# Adafruit_PowerBoost_1000C_Rev_B.net
KiCad netlist of a schematic drawn in EAGLE
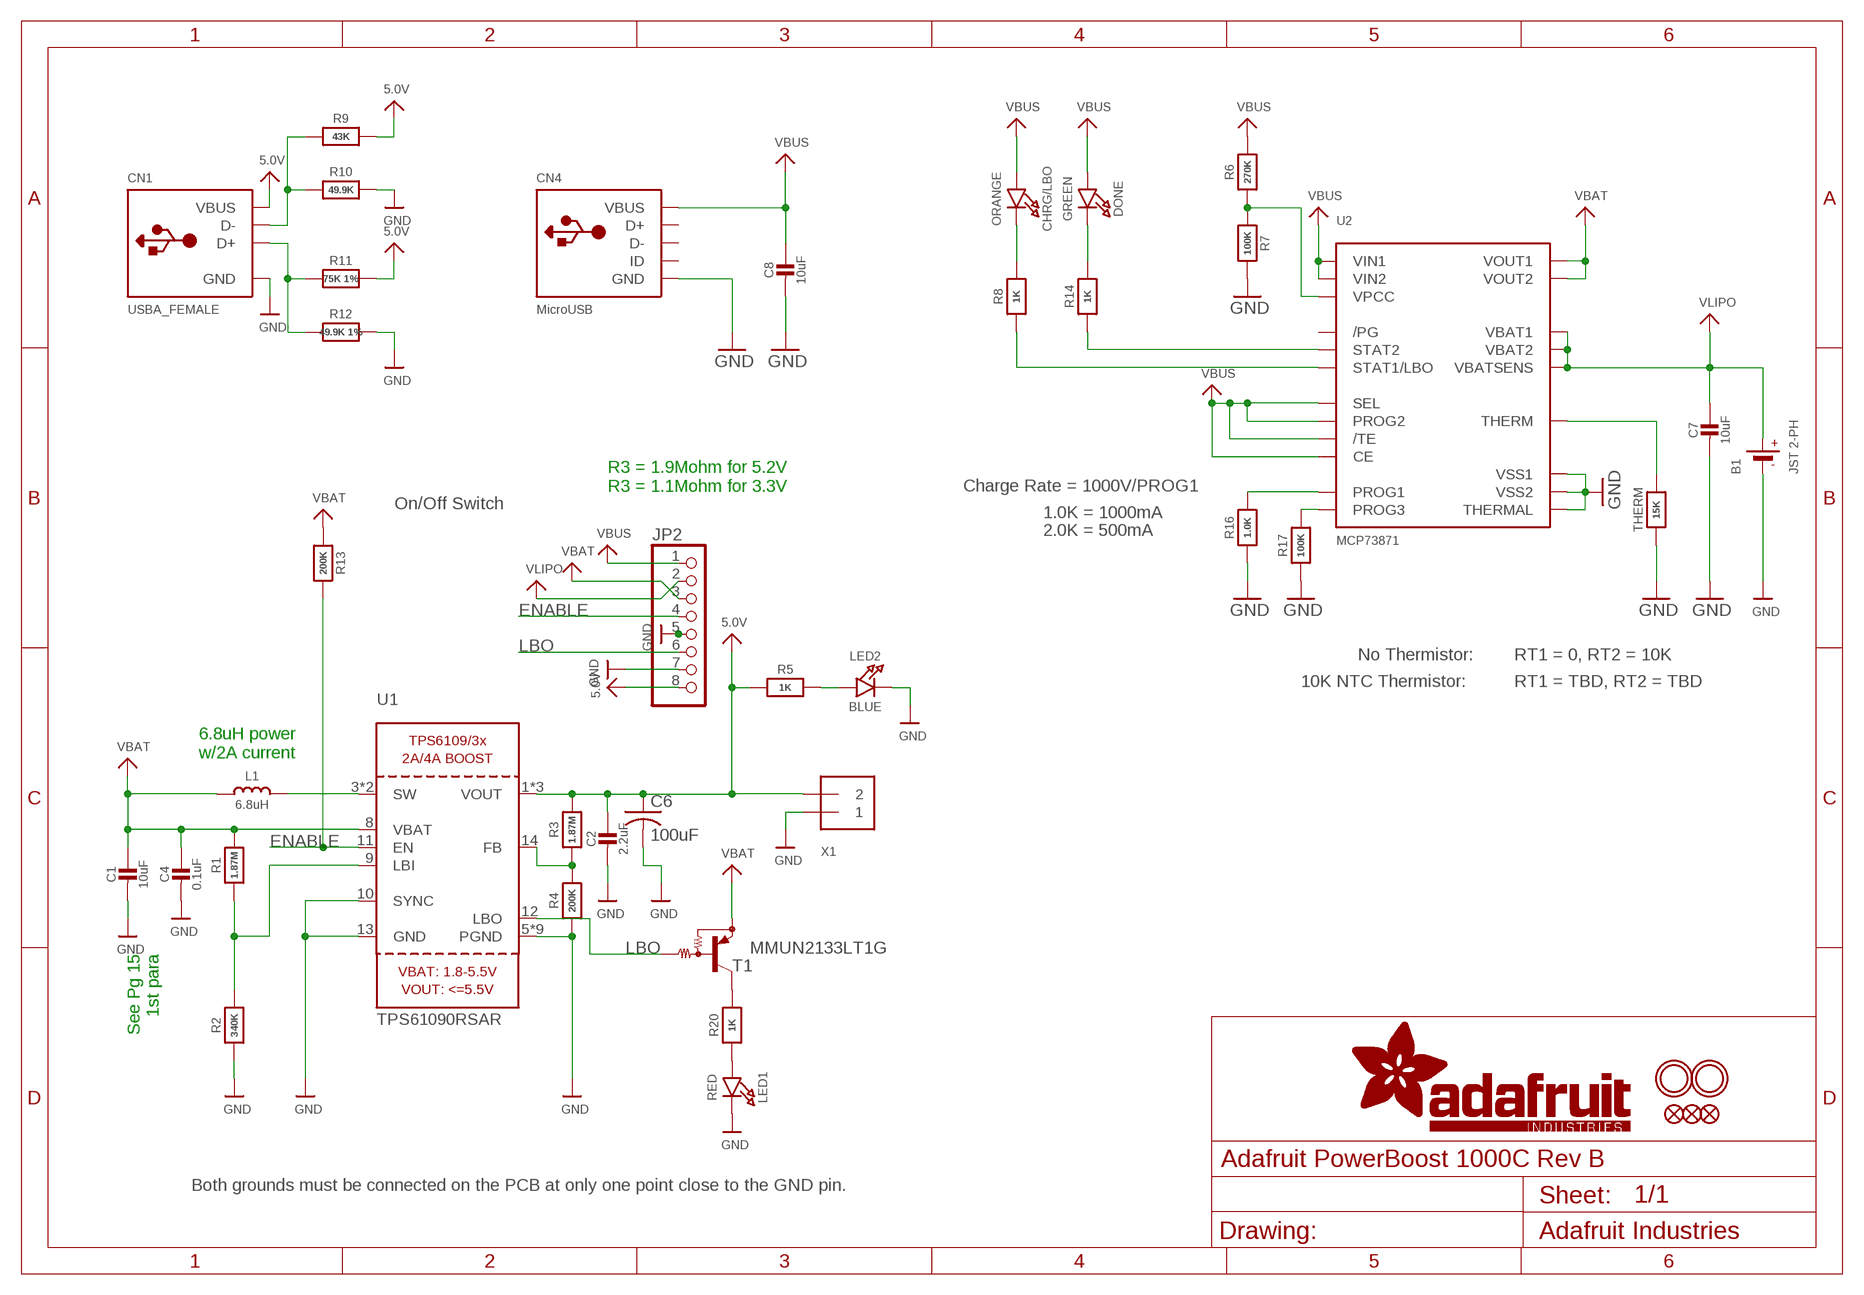
[diagram p0: schematic, sheet 1]

(export (version "E")
  (design (tool "Eeschema 10.0.6"))
  (components
    (comp (ref "B1")
      (value "JST 2-PH")
      (footprint "eagle-import:JSTPH2")
      (libsource (lib "eagle-import") (part "BATTERY"))
    )
    (comp (ref "C1")
      (value "10uF")
      (footprint "eagle-import:0805-NO")
      (libsource (lib "eagle-import") (part "CAP_CERAMIC0805-NOOUTLINE"))
    )
    (comp (ref "C2")
      (value "2.2uF")
      (footprint "eagle-import:0805-NO")
      (libsource (lib "eagle-import") (part "CAP_CERAMIC0805-NOOUTLINE"))
    )
    (comp (ref "C4")
      (value "0.1uF")
      (footprint "eagle-import:0805_10MGAP")
      (libsource (lib "eagle-import") (part "CAP_CERAMIC0805_10MGAP"))
    )
    (comp (ref "C6")
      (value "100uF")
      (footprint "eagle-import:C1210")
      (libsource (lib "eagle-import") (part "C-USC1210"))
    )
    (comp (ref "C7")
      (value "10uF")
      (footprint "eagle-import:0805-NO")
      (libsource (lib "eagle-import") (part "CAP_CERAMIC0805-NOOUTLINE"))
    )
    (comp (ref "C8")
      (value "10uF")
      (footprint "eagle-import:0805-NO")
      (libsource (lib "eagle-import") (part "CAP_CERAMIC0805-NOOUTLINE"))
    )
    (comp (ref "CHRG/LBO")
      (value "ORANGE")
      (footprint "eagle-import:CHIPLED_0805_NOOUTLINE")
      (libsource (lib "eagle-import") (part "LED0805_NOOUTLINE"))
    )
    (comp (ref "CN1")
      (value "USBA_FEMALE")
      (footprint "eagle-import:USB_HOST-PTH")
      (libsource (lib "eagle-import") (part "USB_TYPEAPTHFML"))
    )
    (comp (ref "CN4")
      (value "MicroUSB")
      (footprint "eagle-import:4UCONN_20329")
      (libsource (lib "eagle-import") (part "USBMICRO_20329"))
    )
    (comp (ref "DONE")
      (value "GREEN")
      (footprint "eagle-import:CHIPLED_0805_NOOUTLINE")
      (libsource (lib "eagle-import") (part "LED0805_NOOUTLINE"))
    )
    (comp (ref "FID1")
      (value "FIDUCIAL\"\"")
      (footprint "eagle-import:FIDUCIAL_1MM")
      (fields (field (name "BOM") "EXCLUDE"))
      (libsource (lib "eagle-import") (part "FIDUCIAL{dblquote}{dblquote}"))
    )
    (comp (ref "FID2")
      (value "FIDUCIAL\"\"")
      (footprint "eagle-import:FIDUCIAL_1MM")
      (libsource (lib "eagle-import") (part "FIDUCIAL{dblquote}{dblquote}"))
    )
    (comp (ref "FID3")
      (value "FIDUCIAL\"\"")
      (footprint "eagle-import:FIDUCIAL_1MM")
      (fields (field (name "BOM") "EXCLUDE"))
      (libsource (lib "eagle-import") (part "FIDUCIAL{dblquote}{dblquote}"))
    )
    (comp (ref "JP2")
      (value "HEADER-1X8ROUND")
      (footprint "eagle-import:1X08_ROUND")
      (libsource (lib "eagle-import") (part "HEADER-1X8ROUND"))
    )
    (comp (ref "L1")
      (value "6.8uH")
      (footprint "eagle-import:INDUCTOR_5X5MM_TDK_VLC5045")
      (libsource (lib "eagle-import") (part "INDUCTORTDK_VLC5045"))
    )
    (comp (ref "LED1")
      (value "RED")
      (footprint "eagle-import:CHIPLED_0805_NOOUTLINE")
      (libsource (lib "eagle-import") (part "LED0805_NOOUTLINE"))
    )
    (comp (ref "LED2")
      (value "BLUE")
      (footprint "eagle-import:CHIPLED_0805_NOOUTLINE")
      (libsource (lib "eagle-import") (part "LED0805_NOOUTLINE"))
    )
    (comp (ref "R1")
      (value "1.87M")
      (footprint "eagle-import:_0805MP")
      (libsource (lib "eagle-import") (part "RESISTOR_0805MP"))
    )
    (comp (ref "R2")
      (value "340K")
      (footprint "eagle-import:_0805MP")
      (libsource (lib "eagle-import") (part "RESISTOR_0805MP"))
    )
    (comp (ref "R3")
      (value "1.87M")
      (footprint "eagle-import:0805-NO")
      (libsource (lib "eagle-import") (part "RESISTOR0805_NOOUTLINE"))
    )
    (comp (ref "R4")
      (value "200K")
      (footprint "eagle-import:0805-NO")
      (libsource (lib "eagle-import") (part "RESISTOR0805_NOOUTLINE"))
    )
    (comp (ref "R5")
      (value "1K")
      (footprint "eagle-import:0805-NO")
      (libsource (lib "eagle-import") (part "RESISTOR0805_NOOUTLINE"))
    )
    (comp (ref "R6")
      (value "270K")
      (footprint "eagle-import:0805-NO")
      (libsource (lib "eagle-import") (part "RESISTOR0805_NOOUTLINE"))
    )
    (comp (ref "R7")
      (value "100K")
      (footprint "eagle-import:0805-NO")
      (libsource (lib "eagle-import") (part "RESISTOR0805_NOOUTLINE"))
    )
    (comp (ref "R8")
      (value "1K")
      (footprint "eagle-import:0805-NO")
      (libsource (lib "eagle-import") (part "RESISTOR0805_NOOUTLINE"))
    )
    (comp (ref "R9")
      (value "43K")
      (footprint "eagle-import:0805-NO")
      (libsource (lib "eagle-import") (part "RESISTOR0805_NOOUTLINE"))
    )
    (comp (ref "R10")
      (value "49.9K")
      (footprint "eagle-import:0805-NO")
      (libsource (lib "eagle-import") (part "RESISTOR0805_NOOUTLINE"))
    )
    (comp (ref "R11")
      (value "75K 1%")
      (footprint "eagle-import:0805-NO")
      (libsource (lib "eagle-import") (part "RESISTOR0805_NOOUTLINE"))
    )
    (comp (ref "R12")
      (value "49.9K 1%")
      (footprint "eagle-import:0805-NO")
      (libsource (lib "eagle-import") (part "RESISTOR0805_NOOUTLINE"))
    )
    (comp (ref "R13")
      (value "200K")
      (footprint "eagle-import:0805-NO")
      (libsource (lib "eagle-import") (part "RESISTOR0805_NOOUTLINE"))
    )
    (comp (ref "R14")
      (value "1K")
      (footprint "eagle-import:0805-NO")
      (libsource (lib "eagle-import") (part "RESISTOR0805_NOOUTLINE"))
    )
    (comp (ref "R16")
      (value "1.0K")
      (footprint "eagle-import:0805-NO")
      (libsource (lib "eagle-import") (part "RESISTOR0805_NOOUTLINE"))
    )
    (comp (ref "R17")
      (value "100K")
      (footprint "eagle-import:0805-NO")
      (libsource (lib "eagle-import") (part "RESISTOR0805_NOOUTLINE"))
    )
    (comp (ref "R20")
      (value "1K")
      (footprint "eagle-import:0805-NO")
      (libsource (lib "eagle-import") (part "RESISTOR0805_NOOUTLINE"))
    )
    (comp (ref "T1")
      (value "MMUN2133LT1G")
      (footprint "eagle-import:SC59-BEC")
      (libsource (lib "eagle-import") (part "-PNP_DRIVER-SC59-BECMUN2114T1"))
    )
    (comp (ref "THERM")
      (value "15K")
      (footprint "eagle-import:0805-NO")
      (libsource (lib "eagle-import") (part "RESISTOR0805_NOOUTLINE"))
    )
    (comp (ref "U$10")
      (value "MOUNTINGHOLE2.5")
      (footprint "eagle-import:MOUNTINGHOLE_2.5_PLATED")
      (libsource (lib "eagle-import") (part "MOUNTINGHOLE2.5"))
    )
    (comp (ref "U$11")
      (value "MOUNTINGHOLE2.5")
      (footprint "eagle-import:MOUNTINGHOLE_2.5_PLATED")
      (libsource (lib "eagle-import") (part "MOUNTINGHOLE2.5"))
    )
    (comp (ref "U1")
      (value "TPS61090RSAR")
      (footprint "eagle-import:PVQFN-16")
      (libsource (lib "eagle-import") (part "VREG_TPS6103X"))
    )
    (comp (ref "U2")
      (value "MCP73871")
      (footprint "eagle-import:QFN20_4MM")
      (libsource (lib "eagle-import") (part "MCP73871"))
    )
    (comp (ref "X1")
      (value "TERMBLOCK_1X2")
      (footprint "eagle-import:TERMBLOCK_1X2-3.5MM")
      (libsource (lib "eagle-import") (part "TERMBLOCK_1X2"))
    )
  )
  (nets
    (net (code "1") (name "/ENABLE") (class "Default")
      (node (ref "JP2") (pin "4") (pinfunction "4_4") (pintype "passive"))
      (node (ref "R13") (pin "2") (pinfunction "2_2") (pintype "passive"))
      (node (ref "U1") (pin "11") (pinfunction "EN_11") (pintype "input"))
    )
    (net (code "2") (name "/LBO") (class "Default")
      (node (ref "JP2") (pin "6") (pinfunction "6_6") (pintype "passive"))
      (node (ref "T1") (pin "B") (pinfunction "B_B") (pintype "passive"))
      (node (ref "U1") (pin "12") (pinfunction "LBO_12") (pintype "output"))
    )
    (net (code "3") (name "5.0V") (class "Default")
      (node (ref "C2") (pin "1") (pinfunction "1_1") (pintype "passive"))
      (node (ref "C6") (pin "1") (pinfunction "1_1") (pintype "passive"))
      (node (ref "CN1") (pin "VBUS") (pinfunction "VBUS_VBUS") (pintype "power_in"))
      (node (ref "JP2") (pin "8") (pinfunction "8_8") (pintype "passive"))
      (node (ref "R11") (pin "2") (pinfunction "2_2") (pintype "passive"))
      (node (ref "R3") (pin "2") (pinfunction "2_2") (pintype "passive"))
      (node (ref "R5") (pin "1") (pinfunction "1_1") (pintype "passive"))
      (node (ref "R9") (pin "2") (pinfunction "2_2") (pintype "passive"))
      (node (ref "U1") (pin "1") (pinfunction "VOUT_1") (pintype "power_in"))
      (node (ref "U1") (pin "15") (pinfunction "VOUT_15") (pintype "power_in"))
      (node (ref "U1") (pin "16") (pinfunction "VOUT_16") (pintype "power_in"))
      (node (ref "X1") (pin "2") (pinfunction "2_2") (pintype "passive"))
    )
    (net (code "4") (name "GND") (class "Default")
      (node (ref "B1") (pin "1") (pinfunction "-_1") (pintype "passive"))
      (node (ref "C1") (pin "2") (pinfunction "2_2") (pintype "passive"))
      (node (ref "C2") (pin "2") (pinfunction "2_2") (pintype "passive"))
      (node (ref "C4") (pin "2") (pinfunction "2_2") (pintype "passive"))
      (node (ref "C6") (pin "2") (pinfunction "2_2") (pintype "passive"))
      (node (ref "C7") (pin "2") (pinfunction "2_2") (pintype "passive"))
      (node (ref "C8") (pin "2") (pinfunction "2_2") (pintype "passive"))
      (node (ref "CN1") (pin "GND") (pinfunction "GND_GND") (pintype "power_in"))
      (node (ref "CN4") (pin "BASE@1") (pinfunction "GND_BASE@1") (pintype "power_in"))
      (node (ref "CN4") (pin "BASE@2") (pinfunction "GND_BASE@2") (pintype "power_in"))
      (node (ref "CN4") (pin "GND") (pinfunction "GND_GND") (pintype "power_in"))
      (node (ref "CN4") (pin "SPRT@1") (pinfunction "GND_SPRT@1") (pintype "power_in"))
      (node (ref "CN4") (pin "SPRT@2") (pinfunction "GND_SPRT@2") (pintype "power_in"))
      (node (ref "CN4") (pin "SPRT@3") (pinfunction "GND_SPRT@3") (pintype "power_in"))
      (node (ref "CN4") (pin "SPRT@4") (pinfunction "GND_SPRT@4") (pintype "power_in"))
      (node (ref "JP2") (pin "5") (pinfunction "5_5") (pintype "passive"))
      (node (ref "JP2") (pin "7") (pinfunction "7_7") (pintype "passive"))
      (node (ref "LED1") (pin "C") (pinfunction "C_C") (pintype "passive"))
      (node (ref "LED2") (pin "C") (pinfunction "C_C") (pintype "passive"))
      (node (ref "R10") (pin "2") (pinfunction "2_2") (pintype "passive"))
      (node (ref "R12") (pin "2") (pinfunction "2_2") (pintype "passive"))
      (node (ref "R16") (pin "1") (pinfunction "1_1") (pintype "passive"))
      (node (ref "R17") (pin "1") (pinfunction "1_1") (pintype "passive"))
      (node (ref "R2") (pin "1") (pinfunction "1_1") (pintype "passive"))
      (node (ref "R4") (pin "1") (pinfunction "1_1") (pintype "passive"))
      (node (ref "R7") (pin "2") (pinfunction "2_2") (pintype "passive"))
      (node (ref "THERM") (pin "1") (pinfunction "1_1") (pintype "passive"))
      (node (ref "U1") (pin "10") (pinfunction "SYNC_10") (pintype "input"))
      (node (ref "U1") (pin "13") (pinfunction "GND_13") (pintype "power_in"))
      (node (ref "U1") (pin "5") (pinfunction "PGND_5") (pintype "power_in"))
      (node (ref "U1") (pin "6") (pinfunction "PGND_6") (pintype "power_in"))
      (node (ref "U1") (pin "7") (pinfunction "PGND_7") (pintype "power_in"))
      (node (ref "U1") (pin "P$18") (pinfunction "PGND_P$18") (pintype "power_in"))
      (node (ref "U1") (pin "P$19") (pinfunction "PGND_P$19") (pintype "power_in"))
      (node (ref "U1") (pin "P$20") (pinfunction "PGND_P$20") (pintype "power_in"))
      (node (ref "U1") (pin "P$21") (pinfunction "PGND_P$21") (pintype "power_in"))
      (node (ref "U1") (pin "P$22") (pinfunction "PGND_P$22") (pintype "power_in"))
      (node (ref "U1") (pin "THERMAL") (pinfunction "PGND_THERMAL") (pintype "power_in"))
      (node (ref "U2") (pin "P$10") (pinfunction "VSS1_P$10") (pintype "bidirectional"))
      (node (ref "U2") (pin "P$11") (pinfunction "VSS2_P$11") (pintype "bidirectional"))
      (node (ref "U2") (pin "P$21") (pinfunction "THERMAL_P$21") (pintype "bidirectional"))
      (node (ref "X1") (pin "1") (pinfunction "1_1") (pintype "passive"))
    )
    (net (code "5") (name "Net-(CHRG/LBO-PadC)") (class "Default")
      (node (ref "CHRG/LBO") (pin "C") (pinfunction "C_C") (pintype "passive"))
      (node (ref "R8") (pin "2") (pinfunction "2_2") (pintype "passive"))
    )
    (net (code "6") (name "Net-(CN1-PadD+)") (class "Default")
      (node (ref "CN1") (pin "D+") (pinfunction "D+_D+") (pintype "bidirectional"))
      (node (ref "R11") (pin "1") (pinfunction "1_1") (pintype "passive"))
      (node (ref "R12") (pin "1") (pinfunction "1_1") (pintype "passive"))
    )
    (net (code "7") (name "Net-(CN1-PadD-)") (class "Default")
      (node (ref "CN1") (pin "D-") (pinfunction "D-_D-") (pintype "bidirectional"))
      (node (ref "R10") (pin "1") (pinfunction "1_1") (pintype "passive"))
      (node (ref "R9") (pin "1") (pinfunction "1_1") (pintype "passive"))
    )
    (net (code "8") (name "Net-(DONE-PadC)") (class "Default")
      (node (ref "DONE") (pin "C") (pinfunction "C_C") (pintype "passive"))
      (node (ref "R14") (pin "2") (pinfunction "2_2") (pintype "passive"))
    )
    (net (code "9") (name "Net-(L1-2)") (class "Default")
      (node (ref "L1") (pin "P$2") (pinfunction "2_P$2") (pintype "passive"))
      (node (ref "U1") (pin "3") (pinfunction "SW_3") (pintype "input"))
      (node (ref "U1") (pin "4") (pinfunction "SW_4") (pintype "input"))
    )
    (net (code "10") (name "Net-(LED1-PadA)") (class "Default")
      (node (ref "LED1") (pin "A") (pinfunction "A_A") (pintype "passive"))
      (node (ref "R20") (pin "1") (pinfunction "1_1") (pintype "passive"))
    )
    (net (code "11") (name "Net-(LED2-PadA)") (class "Default")
      (node (ref "LED2") (pin "A") (pinfunction "A_A") (pintype "passive"))
      (node (ref "R5") (pin "2") (pinfunction "2_2") (pintype "passive"))
    )
    (net (code "12") (name "Net-(R20-Pad2)") (class "Default")
      (node (ref "R20") (pin "2") (pinfunction "2_2") (pintype "passive"))
      (node (ref "T1") (pin "C") (pinfunction "C_C") (pintype "passive"))
    )
    (net (code "13") (name "Net-(U1-FB)") (class "Default")
      (node (ref "R3") (pin "1") (pinfunction "1_1") (pintype "passive"))
      (node (ref "R4") (pin "2") (pinfunction "2_2") (pintype "passive"))
      (node (ref "U1") (pin "14") (pinfunction "FB_14") (pintype "input"))
    )
    (net (code "14") (name "Net-(U1-LBI)") (class "Default")
      (node (ref "R1") (pin "1") (pinfunction "1_1") (pintype "passive"))
      (node (ref "R2") (pin "2") (pinfunction "2_2") (pintype "passive"))
      (node (ref "U1") (pin "9") (pinfunction "LBI_9") (pintype "input"))
    )
    (net (code "15") (name "Net-(U2-PROG1)") (class "Default")
      (node (ref "R16") (pin "2") (pinfunction "2_2") (pintype "passive"))
      (node (ref "U2") (pin "P$13") (pinfunction "PROG1_P$13") (pintype "bidirectional"))
    )
    (net (code "16") (name "Net-(U2-PROG3)") (class "Default")
      (node (ref "R17") (pin "2") (pinfunction "2_2") (pintype "passive"))
      (node (ref "U2") (pin "P$12") (pinfunction "PROG3_P$12") (pintype "bidirectional"))
    )
    (net (code "17") (name "Net-(U2-STAT1{slash}LBO)") (class "Default")
      (node (ref "R8") (pin "1") (pinfunction "1_1") (pintype "passive"))
      (node (ref "U2") (pin "P$8") (pinfunction "STAT1/LBO_P$8") (pintype "bidirectional"))
    )
    (net (code "18") (name "Net-(U2-STAT2)") (class "Default")
      (node (ref "R14") (pin "1") (pinfunction "1_1") (pintype "passive"))
      (node (ref "U2") (pin "P$7") (pinfunction "STAT2_P$7") (pintype "bidirectional"))
    )
    (net (code "19") (name "Net-(U2-THERM)") (class "Default")
      (node (ref "THERM") (pin "2") (pinfunction "2_2") (pintype "passive"))
      (node (ref "U2") (pin "P$5") (pinfunction "THERM_P$5") (pintype "bidirectional"))
    )
    (net (code "20") (name "Net-(U2-VPCC)") (class "Default")
      (node (ref "R6") (pin "1") (pinfunction "1_1") (pintype "passive"))
      (node (ref "R7") (pin "1") (pinfunction "1_1") (pintype "passive"))
      (node (ref "U2") (pin "P$2") (pinfunction "VPCC_P$2") (pintype "bidirectional"))
    )
    (net (code "21") (name "VBAT") (class "Default")
      (node (ref "C1") (pin "1") (pinfunction "1_1") (pintype "passive"))
      (node (ref "C4") (pin "1") (pinfunction "1_1") (pintype "passive"))
      (node (ref "JP2") (pin "3") (pinfunction "3_3") (pintype "passive"))
      (node (ref "L1") (pin "P$1") (pinfunction "1_P$1") (pintype "passive"))
      (node (ref "R1") (pin "2") (pinfunction "2_2") (pintype "passive"))
      (node (ref "R13") (pin "1") (pinfunction "1_1") (pintype "passive"))
      (node (ref "T1") (pin "E") (pinfunction "E_E") (pintype "passive"))
      (node (ref "U1") (pin "8") (pinfunction "VBAT_8") (pintype "input"))
      (node (ref "U2") (pin "P$1") (pinfunction "VOUT1_P$1") (pintype "bidirectional"))
      (node (ref "U2") (pin "P$20") (pinfunction "VOUT2_P$20") (pintype "bidirectional"))
    )
    (net (code "22") (name "VBUS") (class "Default")
      (node (ref "C8") (pin "1") (pinfunction "1_1") (pintype "passive"))
      (node (ref "CHRG/LBO") (pin "A") (pinfunction "A_A") (pintype "passive"))
      (node (ref "CN4") (pin "VBUS") (pinfunction "VBUS_VBUS") (pintype "power_in"))
      (node (ref "DONE") (pin "A") (pinfunction "A_A") (pintype "passive"))
      (node (ref "JP2") (pin "1") (pinfunction "1_1") (pintype "passive"))
      (node (ref "R6") (pin "2") (pinfunction "2_2") (pintype "passive"))
      (node (ref "U2") (pin "P$17") (pinfunction "CE_P$17") (pintype "bidirectional"))
      (node (ref "U2") (pin "P$18") (pinfunction "VIN1_P$18") (pintype "bidirectional"))
      (node (ref "U2") (pin "P$19") (pinfunction "VIN2_P$19") (pintype "bidirectional"))
      (node (ref "U2") (pin "P$3") (pinfunction "SEL_P$3") (pintype "bidirectional"))
      (node (ref "U2") (pin "P$4") (pinfunction "PROG2_P$4") (pintype "bidirectional"))
      (node (ref "U2") (pin "P$9") (pinfunction "/TE_P$9") (pintype "bidirectional"))
    )
    (net (code "23") (name "VLIPO") (class "Default")
      (node (ref "B1") (pin "2") (pinfunction "+_2") (pintype "passive"))
      (node (ref "C7") (pin "1") (pinfunction "1_1") (pintype "passive"))
      (node (ref "JP2") (pin "2") (pinfunction "2_2") (pintype "passive"))
      (node (ref "U2") (pin "P$14") (pinfunction "VBAT1_P$14") (pintype "bidirectional"))
      (node (ref "U2") (pin "P$15") (pinfunction "VBAT2_P$15") (pintype "bidirectional"))
      (node (ref "U2") (pin "P$16") (pinfunction "VBATSENS_P$16") (pintype "bidirectional"))
    )
    (net (code "24") (name "unconnected-(CN4-PadD+)") (class "Default")
      (node (ref "CN4") (pin "D+") (pinfunction "D+_D+") (pintype "bidirectional"))
    )
    (net (code "25") (name "unconnected-(CN4-PadD-)") (class "Default")
      (node (ref "CN4") (pin "D-") (pinfunction "D-_D-") (pintype "bidirectional"))
    )
    (net (code "26") (name "unconnected-(CN4-PadID)") (class "Default")
      (node (ref "CN4") (pin "ID") (pinfunction "ID_ID") (pintype "bidirectional"))
    )
    (net (code "27") (name "unconnected-(U2-{slash}PG-PadP$6)") (class "Default")
      (node (ref "U2") (pin "P$6") (pinfunction "/PG_P$6") (pintype "bidirectional"))
    )
  )
)
